# TK522_LV-Trafo.net
KiCad netlist of a schematic drawn in Altium Designer
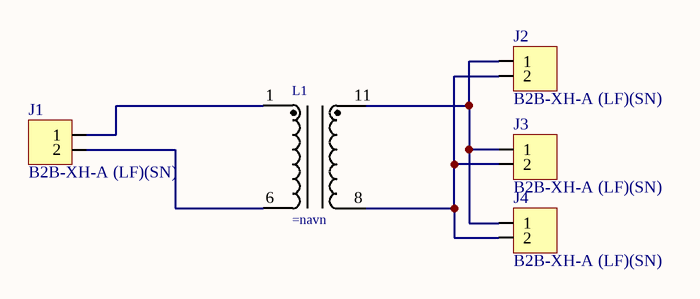
[diagram p0: TK522_LV-Trafo.SchDoc]

(export (version "E")
  (design (tool "Eeschema 10.0.6"))
  (components
    (comp (ref "J1")
      (value "B2B-XH-A (LF)(SN)")
      (footprint "JST_2P")
      (libsource (lib "") (part "2PConnector_1"))
    )
    (comp (ref "J2")
      (value "B2B-XH-A (LF)(SN)")
      (footprint "JST_2P")
      (libsource (lib "OVLib") (part "2PConnector"))
    )
    (comp (ref "J3")
      (value "B2B-XH-A (LF)(SN)")
      (footprint "JST_2P")
      (libsource (lib "OVLib") (part "2PConnector"))
    )
    (comp (ref "J4")
      (value "B2B-XH-A (LF)(SN)")
      (footprint "JST_2P")
      (libsource (lib "OVLib") (part "2PConnector"))
    )
    (comp (ref "L1")
      (value "~")
      (footprint "44268 MYRRA TRANSFORMER")
      (libsource (lib "44268 Myrra Transformer") (part "44268 Myrra Transformer"))
    )
  )
  (nets
    (net (code "1") (name "Net-(J1-Pad1)") (class "Default")
      (node (ref "J1") (pin "1") (pinfunction "1_1") (pintype "passive"))
      (node (ref "L1") (pin "1") (pinfunction "1_1") (pintype "passive"))
    )
    (net (code "2") (name "Net-(J1-Pad2)") (class "Default")
      (node (ref "J1") (pin "2") (pinfunction "2_2") (pintype "passive"))
      (node (ref "L1") (pin "6") (pinfunction "6_6") (pintype "passive"))
    )
    (net (code "3") (name "Net-(J2-Pad1)") (class "Default")
      (node (ref "J2") (pin "1") (pinfunction "1_1") (pintype "passive"))
      (node (ref "J3") (pin "1") (pinfunction "1_1") (pintype "passive"))
      (node (ref "J4") (pin "1") (pinfunction "1_1") (pintype "passive"))
      (node (ref "L1") (pin "11") (pinfunction "11_11") (pintype "passive"))
    )
    (net (code "4") (name "Net-(J2-Pad2)") (class "Default")
      (node (ref "J2") (pin "2") (pinfunction "2_2") (pintype "passive"))
      (node (ref "J3") (pin "2") (pinfunction "2_2") (pintype "passive"))
      (node (ref "J4") (pin "2") (pinfunction "2_2") (pintype "passive"))
      (node (ref "L1") (pin "8") (pinfunction "8_8") (pintype "passive"))
    )
  )
)
